# SCH_everglow.net
KiCad netlist of a schematic drawn in EasyEDA
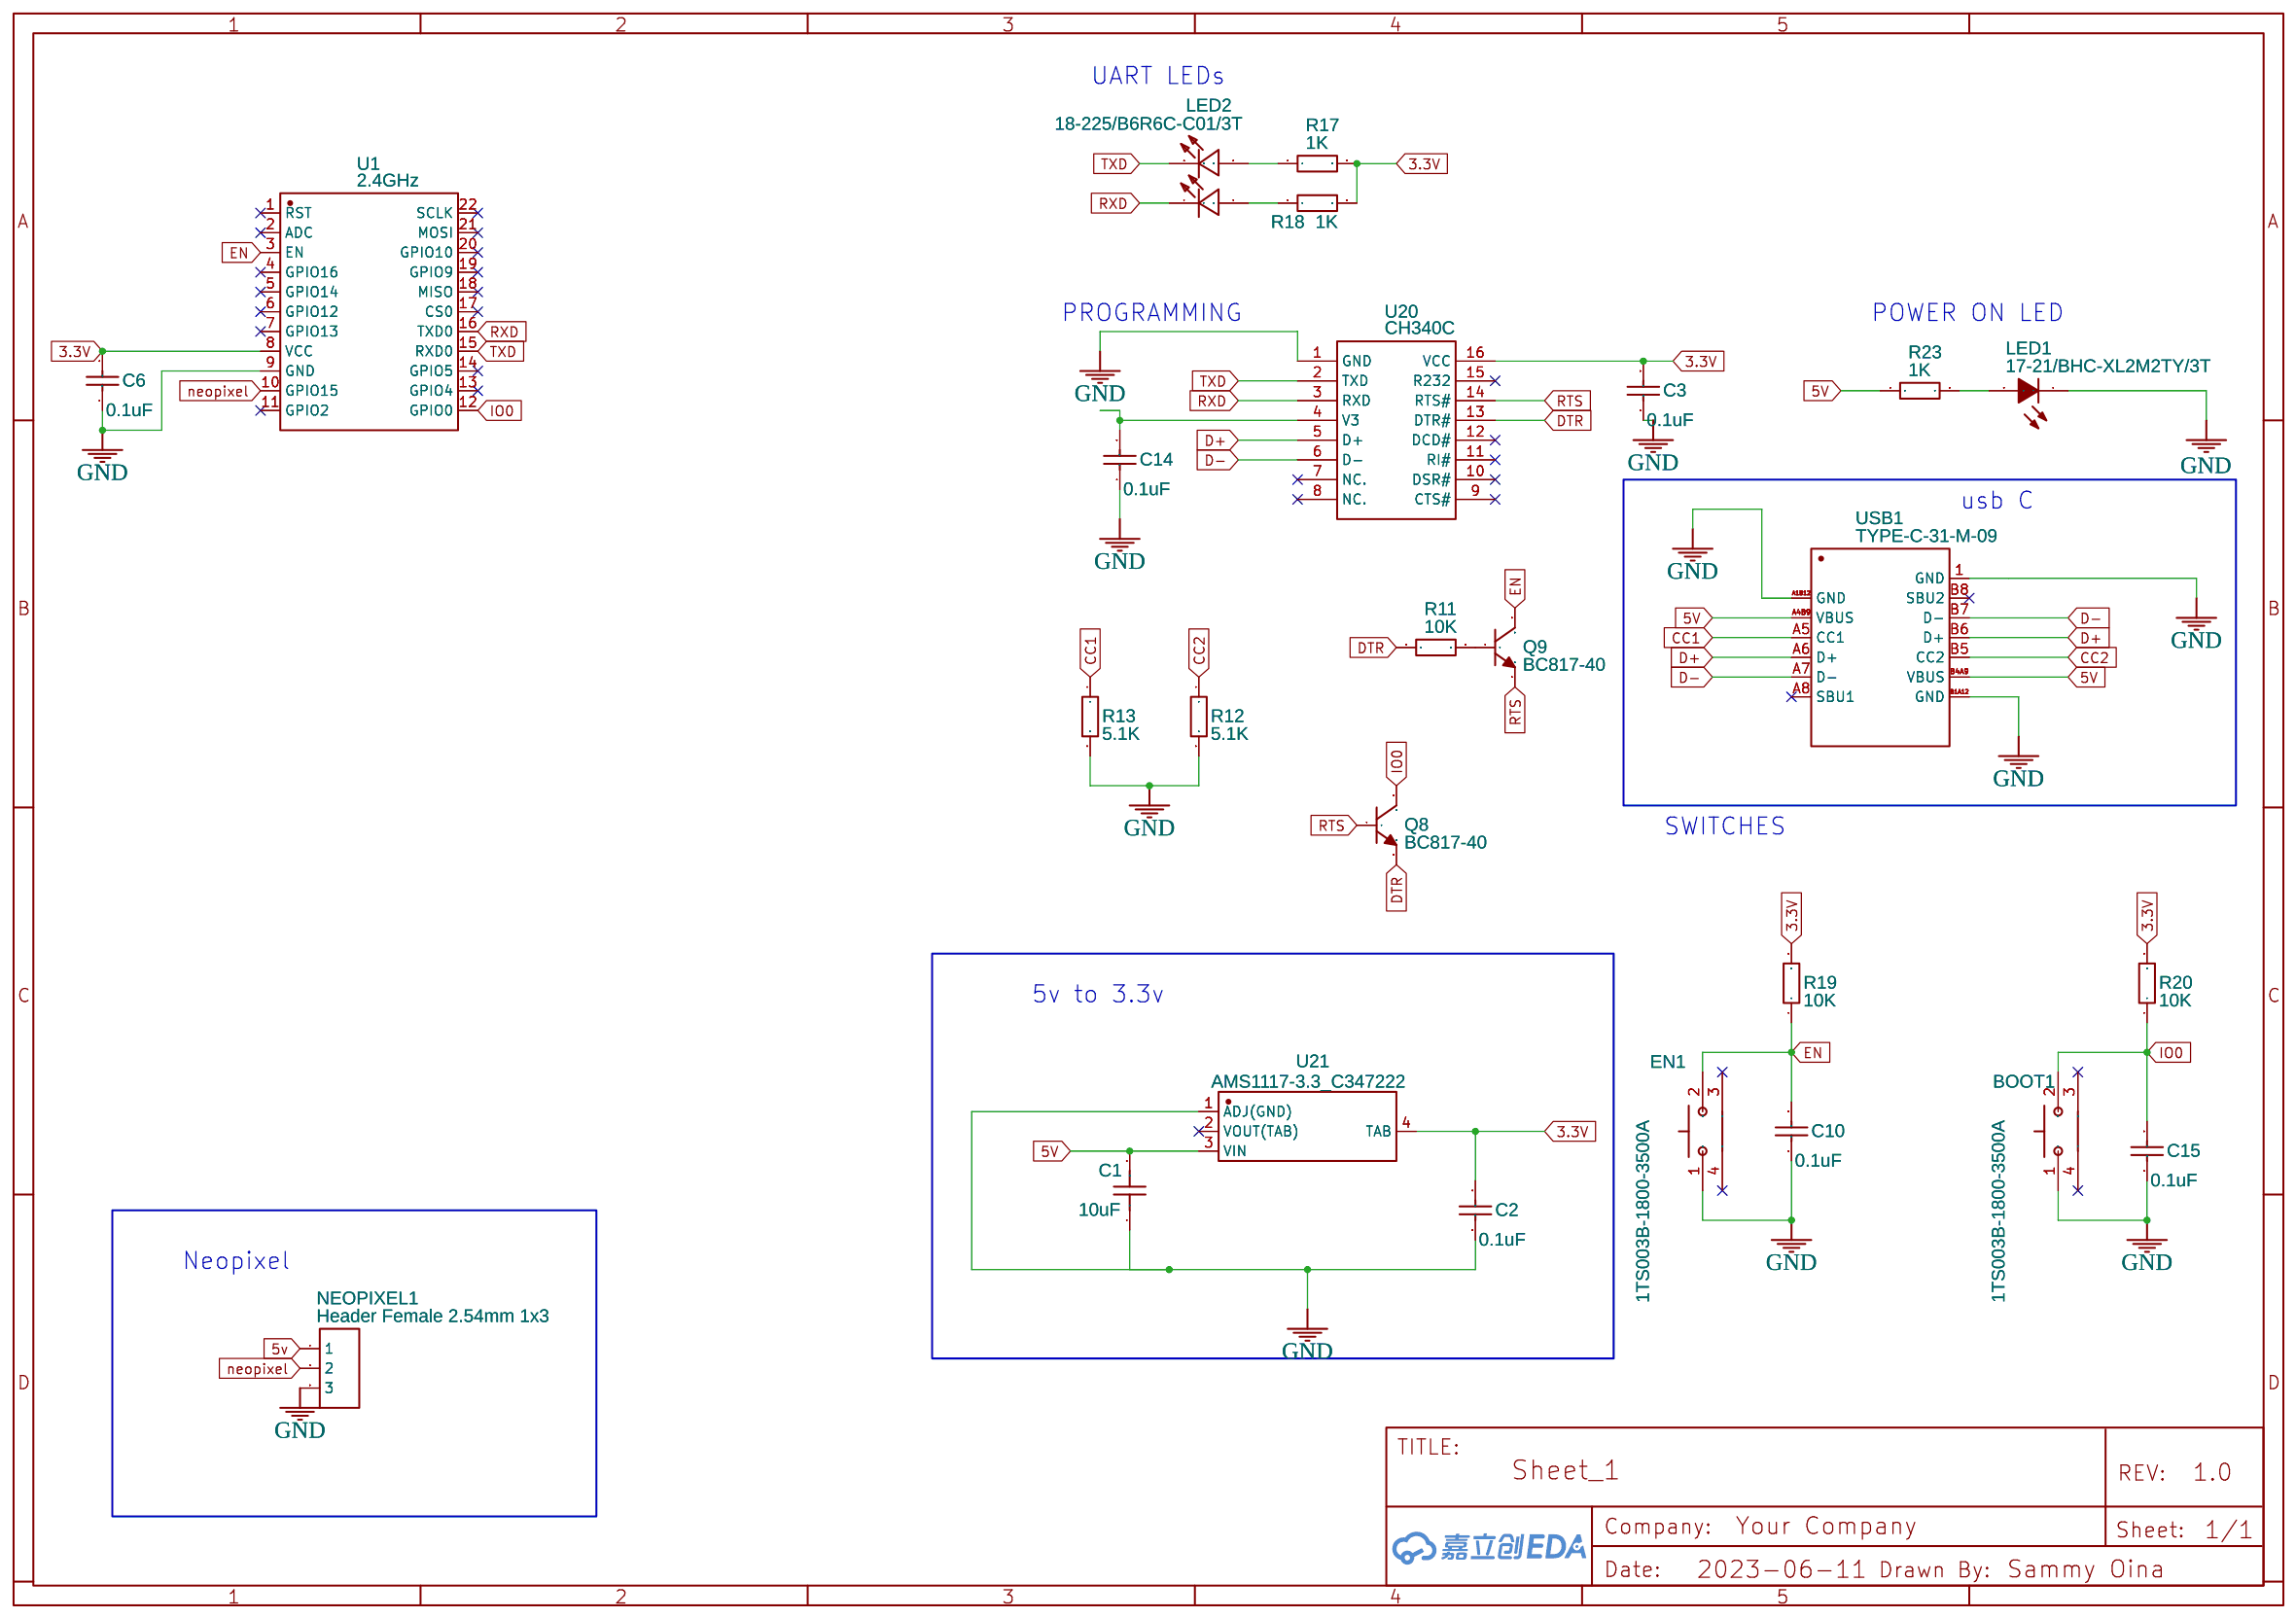
[diagram p0: schematic sheet]

(export (version "E")
  (design (tool "Eeschema 10.0.6"))
  (components
    (comp (ref "BOOT1")
      (value "1TS003B-1800-3500A")
      (fields (field (name "BOM_Supplier Part") "C255809"))
      (libsource (lib "") (part "1TS003B-1800-3500A_1"))
    )
    (comp (ref "C1")
      (value "10uF")
      (fields
        (field (name "BOM_Manufacturer Part") "CL05A106MQ8NUB8")
        (field (name "BOM_Supplier Part") "C307416")
      )
      (libsource (lib "") (part "CL05A106MQ8NUB8"))
    )
    (comp (ref "C2")
      (value "0.1uF")
      (fields
        (field (name "BOM_Manufacturer Part") "0603B104K250")
        (field (name "BOM_Supplier Part") "C83054")
      )
      (libsource (lib "") (part "0603B104K250"))
    )
    (comp (ref "C3")
      (value "0.1uF")
      (fields
        (field (name "BOM_Manufacturer Part") "0603B104K250")
        (field (name "BOM_Supplier Part") "C83054")
      )
      (libsource (lib "") (part "0603B104K250"))
    )
    (comp (ref "C6")
      (value "0.1uF")
      (fields
        (field (name "BOM_Manufacturer Part") "0603B104K250")
        (field (name "BOM_Supplier Part") "C83054")
      )
      (libsource (lib "") (part "0603B104K250"))
    )
    (comp (ref "C10")
      (value "0.1uF")
      (fields
        (field (name "BOM_Manufacturer Part") "0603B104K250")
        (field (name "BOM_Supplier Part") "C83054")
      )
      (libsource (lib "") (part "0603B104K250"))
    )
    (comp (ref "C14")
      (value "0.1uF")
      (fields
        (field (name "BOM_Manufacturer Part") "0603B104K250")
        (field (name "BOM_Supplier Part") "C83054")
      )
      (libsource (lib "") (part "0603B104K250"))
    )
    (comp (ref "C15")
      (value "0.1uF")
      (fields
        (field (name "BOM_Manufacturer Part") "0603B104K250")
        (field (name "BOM_Supplier Part") "C83054")
      )
      (libsource (lib "") (part "0603B104K250"))
    )
    (comp (ref "EN1")
      (value "1TS003B-1800-3500A")
      (fields (field (name "BOM_Supplier Part") "C255809"))
      (libsource (lib "") (part "1TS003B-1800-3500A"))
    )
    (comp (ref "LED1")
      (value "17-21/BHC-XL2M2TY/3T")
      (fields (field (name "BOM_Supplier Part") "C72035"))
      (libsource (lib "") (part "17-21/BHC-XL2M2TY/3T"))
    )
    (comp (ref "LED2")
      (value "18-225/B6R6C-C01/3T")
      (fields (field (name "BOM_Supplier Part") "C282127"))
      (libsource (lib "") (part "18-225/B6R6C-C01/3T"))
    )
    (comp (ref "NEOPIXEL1")
      (value "Header Female 2.54mm 1x3")
      (fields
        (field (name "BOM_Manufacturer Part") "Header-Female-2.54_1x3")
        (field (name "BOM_Supplier Part") "C146243")
      )
      (libsource (lib "") (part "Header Female 2.54mm 1x3"))
    )
    (comp (ref "Q8")
      (value "BC817-40")
      (fields (field (name "BOM_Supplier Part") "C181151"))
      (libsource (lib "") (part "BC817-40"))
    )
    (comp (ref "Q9")
      (value "BC817-40")
      (fields (field (name "BOM_Supplier Part") "C181151"))
      (libsource (lib "") (part "BC817-40"))
    )
    (comp (ref "R11")
      (value "10K")
      (fields
        (field (name "BOM_Manufacturer Part") "0402WGJ0103TCE")
        (field (name "BOM_Supplier Part") "C25531")
      )
      (libsource (lib "") (part "0402WGJ0103TCE_1"))
    )
    (comp (ref "R12")
      (value "5.1K")
      (fields
        (field (name "BOM_Manufacturer Part") "0402WGF5101TCE")
        (field (name "BOM_Supplier Part") "C25905")
      )
      (libsource (lib "") (part "0402WGF5101TCE"))
    )
    (comp (ref "R13")
      (value "5.1K")
      (fields
        (field (name "BOM_Manufacturer Part") "0402WGF5101TCE")
        (field (name "BOM_Supplier Part") "C25905")
      )
      (libsource (lib "") (part "0402WGF5101TCE"))
    )
    (comp (ref "R17")
      (value "1K")
      (fields
        (field (name "BOM_Manufacturer Part") "PTFR0805B1K00N9")
        (field (name "BOM_Supplier Part") "C328437")
      )
      (libsource (lib "") (part "PTFR0805B1K00N9"))
    )
    (comp (ref "R18")
      (value "1K")
      (fields
        (field (name "BOM_Manufacturer Part") "PTFR0805B1K00N9")
        (field (name "BOM_Supplier Part") "C328437")
      )
      (libsource (lib "") (part "PTFR0805B1K00N9"))
    )
    (comp (ref "R19")
      (value "10K")
      (fields
        (field (name "BOM_Manufacturer Part") "0402WGJ0103TCE")
        (field (name "BOM_Supplier Part") "C25531")
      )
      (libsource (lib "") (part "0402WGJ0103TCE"))
    )
    (comp (ref "R20")
      (value "10K")
      (fields
        (field (name "BOM_Manufacturer Part") "0402WGJ0103TCE")
        (field (name "BOM_Supplier Part") "C25531")
      )
      (libsource (lib "") (part "0402WGJ0103TCE"))
    )
    (comp (ref "R23")
      (value "1K")
      (fields
        (field (name "BOM_Manufacturer Part") "PTFR0805B1K00N9")
        (field (name "BOM_Supplier Part") "C328437")
      )
      (libsource (lib "") (part "PTFR0805B1K00N9"))
    )
    (comp (ref "U1")
      (value "2.4GHz")
      (fields
        (field (name "BOM_Manufacturer Part") "ESP-12F(ESP8266MOD)")
        (field (name "BOM_Supplier Part") "C82891")
      )
      (libsource (lib "") (part "ESP-12F(ESP8266MOD)"))
    )
    (comp (ref "U20")
      (value "CH340C")
      (fields (field (name "BOM_Supplier Part") "C84681"))
      (libsource (lib "") (part "CH340C"))
    )
    (comp (ref "U21")
      (value "AMS1117-3.3_C347222")
      (fields
        (field (name "BOM_Manufacturer Part") "AMS1117-3.3")
        (field (name "BOM_Supplier Part") "C347222")
      )
      (libsource (lib "") (part "AMS1117-3.3_C347222"))
    )
    (comp (ref "USB1")
      (value "TYPE-C-31-M-09")
      (fields (field (name "BOM_Supplier Part") "C2689967"))
      (libsource (lib "") (part "TYPE-C-31-M-09"))
    )
  )
  (nets
    (net (code "1") (name "3.3V") (class "Default")
      (node (ref "C2") (pin "2") (pinfunction "2_2") (pintype "input"))
      (node (ref "C3") (pin "2") (pinfunction "2_2") (pintype "input"))
      (node (ref "C6") (pin "2") (pinfunction "2_2") (pintype "input"))
      (node (ref "R17") (pin "2") (pinfunction "2_2") (pintype "unspecified"))
      (node (ref "R18") (pin "2") (pinfunction "2_2") (pintype "unspecified"))
      (node (ref "R19") (pin "2") (pinfunction "2_2") (pintype "input"))
      (node (ref "R20") (pin "2") (pinfunction "2_2") (pintype "input"))
      (node (ref "U1") (pin "8") (pinfunction "VCC_8") (pintype "unspecified"))
      (node (ref "U20") (pin "16") (pinfunction "VCC_16") (pintype "unspecified"))
      (node (ref "U21") (pin "4") (pinfunction "TAB_4") (pintype "unspecified"))
    )
    (net (code "2") (name "5V") (class "Default")
      (node (ref "C1") (pin "2") (pinfunction "2_2") (pintype "unspecified"))
      (node (ref "R23") (pin "1") (pinfunction "1_1") (pintype "unspecified"))
      (node (ref "U21") (pin "3") (pinfunction "VIN_3") (pintype "unspecified"))
      (node (ref "USB1") (pin "A4B9") (pinfunction "VBUS_A4B9") (pintype "unspecified"))
      (node (ref "USB1") (pin "B4A9") (pinfunction "VBUS_B4A9") (pintype "unspecified"))
    )
    (net (code "3") (name "5v") (class "Default")
      (node (ref "NEOPIXEL1") (pin "1") (pinfunction "1_1") (pintype "input"))
    )
    (net (code "4") (name "CC1") (class "Default")
      (node (ref "R13") (pin "1") (pinfunction "1_1") (pintype "input"))
      (node (ref "USB1") (pin "A5") (pinfunction "CC1_A5") (pintype "unspecified"))
    )
    (net (code "5") (name "CC2") (class "Default")
      (node (ref "R12") (pin "1") (pinfunction "1_1") (pintype "input"))
      (node (ref "USB1") (pin "B5") (pinfunction "CC2_B5") (pintype "unspecified"))
    )
    (net (code "6") (name "D+") (class "Default")
      (node (ref "U20") (pin "5") (pinfunction "D+_5") (pintype "unspecified"))
      (node (ref "USB1") (pin "A6") (pinfunction "D+_A6") (pintype "unspecified"))
      (node (ref "USB1") (pin "B6") (pinfunction "D+_B6") (pintype "unspecified"))
    )
    (net (code "7") (name "D-") (class "Default")
      (node (ref "U20") (pin "6") (pinfunction "D-_6") (pintype "unspecified"))
      (node (ref "USB1") (pin "A7") (pinfunction "D-_A7") (pintype "unspecified"))
      (node (ref "USB1") (pin "B7") (pinfunction "D-_B7") (pintype "unspecified"))
    )
    (net (code "8") (name "DTR") (class "Default")
      (node (ref "Q8") (pin "2") (pinfunction "2_2") (pintype "input"))
      (node (ref "R11") (pin "1") (pinfunction "1_1") (pintype "input"))
      (node (ref "U20") (pin "13") (pinfunction "DTR#_13") (pintype "unspecified"))
    )
    (net (code "9") (name "EN") (class "Default")
      (node (ref "C10") (pin "2") (pinfunction "2_2") (pintype "input"))
      (node (ref "EN1") (pin "2") (pinfunction "2_2") (pintype "unspecified"))
      (node (ref "Q9") (pin "3") (pinfunction "3_3") (pintype "input"))
      (node (ref "R19") (pin "1") (pinfunction "1_1") (pintype "input"))
      (node (ref "U1") (pin "3") (pinfunction "EN_3") (pintype "unspecified"))
    )
    (net (code "10") (name "GND") (class "Default")
      (node (ref "BOOT1") (pin "1") (pinfunction "1_1") (pintype "unspecified"))
      (node (ref "C1") (pin "1") (pinfunction "1_1") (pintype "unspecified"))
      (node (ref "C10") (pin "1") (pinfunction "1_1") (pintype "input"))
      (node (ref "C14") (pin "1") (pinfunction "1_1") (pintype "input"))
      (node (ref "C15") (pin "1") (pinfunction "1_1") (pintype "input"))
      (node (ref "C2") (pin "1") (pinfunction "1_1") (pintype "input"))
      (node (ref "C3") (pin "1") (pinfunction "1_1") (pintype "input"))
      (node (ref "C6") (pin "1") (pinfunction "1_1") (pintype "input"))
      (node (ref "EN1") (pin "1") (pinfunction "1_1") (pintype "unspecified"))
      (node (ref "LED1") (pin "1") (pinfunction "-_1") (pintype "input"))
      (node (ref "NEOPIXEL1") (pin "3") (pinfunction "3_3") (pintype "input"))
      (node (ref "R12") (pin "2") (pinfunction "2_2") (pintype "input"))
      (node (ref "R13") (pin "2") (pinfunction "2_2") (pintype "input"))
      (node (ref "U1") (pin "9") (pinfunction "GND_9") (pintype "unspecified"))
      (node (ref "U20") (pin "1") (pinfunction "GND_1") (pintype "unspecified"))
      (node (ref "U21") (pin "1") (pinfunction "ADJ(GND)_1") (pintype "unspecified"))
      (node (ref "USB1") (pin "1") (pinfunction "GND_1") (pintype "unspecified"))
      (node (ref "USB1") (pin "A1B12") (pinfunction "GND_A1B12") (pintype "unspecified"))
      (node (ref "USB1") (pin "B1A12") (pinfunction "GND_B1A12") (pintype "unspecified"))
    )
    (net (code "11") (name "IO0") (class "Default")
      (node (ref "BOOT1") (pin "2") (pinfunction "2_2") (pintype "unspecified"))
      (node (ref "C15") (pin "2") (pinfunction "2_2") (pintype "input"))
      (node (ref "Q8") (pin "3") (pinfunction "3_3") (pintype "input"))
      (node (ref "R20") (pin "1") (pinfunction "1_1") (pintype "input"))
      (node (ref "U1") (pin "12") (pinfunction "GPIO0_12") (pintype "unspecified"))
    )
    (net (code "12") (name "Net-(LED1-+)") (class "Default")
      (node (ref "LED1") (pin "2") (pinfunction "+_2") (pintype "input"))
      (node (ref "R23") (pin "2") (pinfunction "2_2") (pintype "unspecified"))
    )
    (net (code "13") (name "Net-(LED2-Pad1)") (class "Default")
      (node (ref "LED2") (pin "1") (pinfunction "1_1") (pintype "unspecified"))
      (node (ref "R18") (pin "1") (pinfunction "1_1") (pintype "unspecified"))
    )
    (net (code "14") (name "Net-(LED2-Pad2)") (class "Default")
      (node (ref "LED2") (pin "2") (pinfunction "2_2") (pintype "unspecified"))
      (node (ref "R17") (pin "1") (pinfunction "1_1") (pintype "unspecified"))
    )
    (net (code "15") (name "Net-(Q9-Pad1)") (class "Default")
      (node (ref "Q9") (pin "1") (pinfunction "1_1") (pintype "input"))
      (node (ref "R11") (pin "2") (pinfunction "2_2") (pintype "input"))
    )
    (net (code "16") (name "Net-(U20-V3)") (class "Default")
      (node (ref "C14") (pin "2") (pinfunction "2_2") (pintype "input"))
      (node (ref "U20") (pin "4") (pinfunction "V3_4") (pintype "unspecified"))
    )
    (net (code "17") (name "RTS") (class "Default")
      (node (ref "Q8") (pin "1") (pinfunction "1_1") (pintype "input"))
      (node (ref "Q9") (pin "2") (pinfunction "2_2") (pintype "input"))
      (node (ref "U20") (pin "14") (pinfunction "RTS#_14") (pintype "unspecified"))
    )
    (net (code "18") (name "RXD") (class "Default")
      (node (ref "LED2") (pin "4") (pinfunction "4_4") (pintype "unspecified"))
      (node (ref "U1") (pin "16") (pinfunction "TXD0_16") (pintype "unspecified"))
      (node (ref "U20") (pin "3") (pinfunction "RXD_3") (pintype "unspecified"))
    )
    (net (code "19") (name "TXD") (class "Default")
      (node (ref "LED2") (pin "3") (pinfunction "3_3") (pintype "unspecified"))
      (node (ref "U1") (pin "15") (pinfunction "RXD0_15") (pintype "unspecified"))
      (node (ref "U20") (pin "2") (pinfunction "TXD_2") (pintype "unspecified"))
    )
    (net (code "20") (name "neopixel") (class "Default")
      (node (ref "NEOPIXEL1") (pin "2") (pinfunction "2_2") (pintype "input"))
      (node (ref "U1") (pin "10") (pinfunction "GPIO15_10") (pintype "unspecified"))
    )
    (net (code "21") (name "unconnected-(BOOT1-Pad3)") (class "Default")
      (node (ref "BOOT1") (pin "3") (pinfunction "3_3") (pintype "unspecified+no_connect"))
    )
    (net (code "22") (name "unconnected-(BOOT1-Pad4)") (class "Default")
      (node (ref "BOOT1") (pin "4") (pinfunction "4_4") (pintype "unspecified+no_connect"))
    )
    (net (code "23") (name "unconnected-(EN1-Pad3)") (class "Default")
      (node (ref "EN1") (pin "3") (pinfunction "3_3") (pintype "unspecified+no_connect"))
    )
    (net (code "24") (name "unconnected-(EN1-Pad4)") (class "Default")
      (node (ref "EN1") (pin "4") (pinfunction "4_4") (pintype "unspecified+no_connect"))
    )
    (net (code "25") (name "unconnected-(U1-ADC-Pad2)") (class "Default")
      (node (ref "U1") (pin "2") (pinfunction "ADC_2") (pintype "unspecified+no_connect"))
    )
    (net (code "26") (name "unconnected-(U1-CS0-Pad17)") (class "Default")
      (node (ref "U1") (pin "17") (pinfunction "CS0_17") (pintype "unspecified+no_connect"))
    )
    (net (code "27") (name "unconnected-(U1-GPIO2-Pad11)") (class "Default")
      (node (ref "U1") (pin "11") (pinfunction "GPIO2_11") (pintype "unspecified+no_connect"))
    )
    (net (code "28") (name "unconnected-(U1-GPIO4-Pad13)") (class "Default")
      (node (ref "U1") (pin "13") (pinfunction "GPIO4_13") (pintype "unspecified+no_connect"))
    )
    (net (code "29") (name "unconnected-(U1-GPIO5-Pad14)") (class "Default")
      (node (ref "U1") (pin "14") (pinfunction "GPIO5_14") (pintype "unspecified+no_connect"))
    )
    (net (code "30") (name "unconnected-(U1-GPIO9-Pad19)") (class "Default")
      (node (ref "U1") (pin "19") (pinfunction "GPIO9_19") (pintype "unspecified+no_connect"))
    )
    (net (code "31") (name "unconnected-(U1-GPIO10-Pad20)") (class "Default")
      (node (ref "U1") (pin "20") (pinfunction "GPIO10_20") (pintype "unspecified+no_connect"))
    )
    (net (code "32") (name "unconnected-(U1-GPIO12-Pad6)") (class "Default")
      (node (ref "U1") (pin "6") (pinfunction "GPIO12_6") (pintype "unspecified+no_connect"))
    )
    (net (code "33") (name "unconnected-(U1-GPIO13-Pad7)") (class "Default")
      (node (ref "U1") (pin "7") (pinfunction "GPIO13_7") (pintype "unspecified+no_connect"))
    )
    (net (code "34") (name "unconnected-(U1-GPIO14-Pad5)") (class "Default")
      (node (ref "U1") (pin "5") (pinfunction "GPIO14_5") (pintype "unspecified+no_connect"))
    )
    (net (code "35") (name "unconnected-(U1-GPIO16-Pad4)") (class "Default")
      (node (ref "U1") (pin "4") (pinfunction "GPIO16_4") (pintype "unspecified+no_connect"))
    )
    (net (code "36") (name "unconnected-(U1-MISO-Pad18)") (class "Default")
      (node (ref "U1") (pin "18") (pinfunction "MISO_18") (pintype "unspecified+no_connect"))
    )
    (net (code "37") (name "unconnected-(U1-MOSI-Pad21)") (class "Default")
      (node (ref "U1") (pin "21") (pinfunction "MOSI_21") (pintype "unspecified+no_connect"))
    )
    (net (code "38") (name "unconnected-(U1-RST-Pad1)") (class "Default")
      (node (ref "U1") (pin "1") (pinfunction "RST_1") (pintype "unspecified+no_connect"))
    )
    (net (code "39") (name "unconnected-(U1-SCLK-Pad22)") (class "Default")
      (node (ref "U1") (pin "22") (pinfunction "SCLK_22") (pintype "unspecified+no_connect"))
    )
    (net (code "40") (name "unconnected-(U20-CTS#-Pad9)") (class "Default")
      (node (ref "U20") (pin "9") (pinfunction "CTS#_9") (pintype "unspecified+no_connect"))
    )
    (net (code "41") (name "unconnected-(U20-DCD#-Pad12)") (class "Default")
      (node (ref "U20") (pin "12") (pinfunction "DCD#_12") (pintype "unspecified+no_connect"))
    )
    (net (code "42") (name "unconnected-(U20-DSR#-Pad10)") (class "Default")
      (node (ref "U20") (pin "10") (pinfunction "DSR#_10") (pintype "unspecified+no_connect"))
    )
    (net (code "43") (name "unconnected-(U20-NC.-Pad7)") (class "Default")
      (node (ref "U20") (pin "7") (pinfunction "NC._7") (pintype "unspecified+no_connect"))
    )
    (net (code "44") (name "unconnected-(U20-NC.-Pad8)") (class "Default")
      (node (ref "U20") (pin "8") (pinfunction "NC._8") (pintype "unspecified+no_connect"))
    )
    (net (code "45") (name "unconnected-(U20-R232-Pad15)") (class "Default")
      (node (ref "U20") (pin "15") (pinfunction "R232_15") (pintype "unspecified+no_connect"))
    )
    (net (code "46") (name "unconnected-(U20-RI#-Pad11)") (class "Default")
      (node (ref "U20") (pin "11") (pinfunction "RI#_11") (pintype "unspecified+no_connect"))
    )
    (net (code "47") (name "unconnected-(U21-VOUT(TAB)-Pad2)") (class "Default")
      (node (ref "U21") (pin "2") (pinfunction "VOUT(TAB)_2") (pintype "unspecified+no_connect"))
    )
    (net (code "48") (name "unconnected-(USB1-SBU1-PadA8)") (class "Default")
      (node (ref "USB1") (pin "A8") (pinfunction "SBU1_A8") (pintype "unspecified+no_connect"))
    )
    (net (code "49") (name "unconnected-(USB1-SBU2-PadB8)") (class "Default")
      (node (ref "USB1") (pin "B8") (pinfunction "SBU2_B8") (pintype "unspecified+no_connect"))
    )
  )
)
